# Power02.net
KiCad netlist of a schematic drawn in Altium Designer
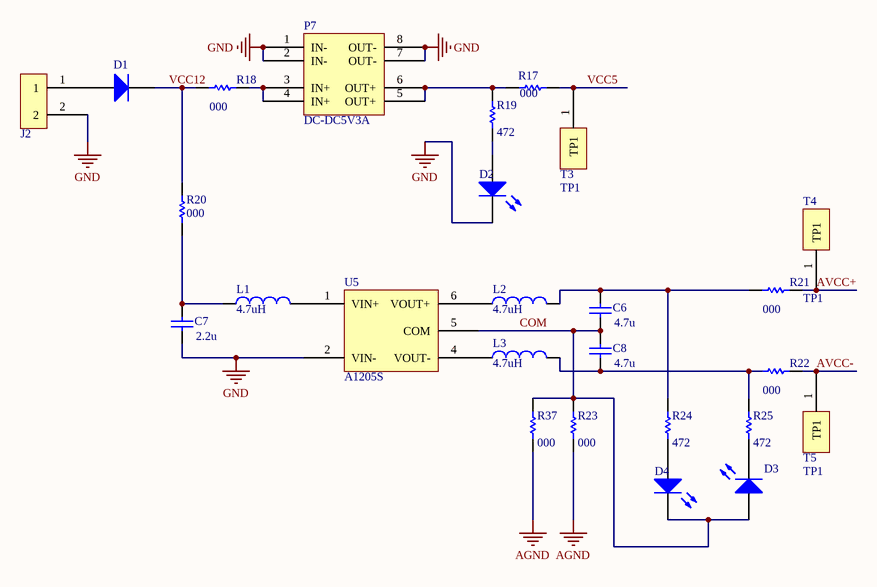
[diagram p0: Power02.SchDoc]

(export (version "E")
  (design (tool "Eeschema 10.0.6"))
  (components
    (comp (ref "C6")
      (value "4.7u")
      (footprint "1206")
      (description "Capacitor (Semiconductor SIM Model)")
      (fields (field (name "Comment") "Cap Semi") (field (name "PUBLISHER") "Altium Limited"))
      (libsource (lib "Miscellaneous Devices") (part "Cap Semi"))
    )
    (comp (ref "C7")
      (value "2.2u")
      (footprint "1206")
      (description "Capacitor (Semiconductor SIM Model)")
      (fields (field (name "Comment") "Cap Semi") (field (name "PUBLISHER") "Altium Limited"))
      (libsource (lib "Miscellaneous Devices") (part "Cap Semi"))
    )
    (comp (ref "C8")
      (value "4.7u")
      (footprint "1206")
      (description "Capacitor (Semiconductor SIM Model)")
      (fields (field (name "Comment") "Cap Semi") (field (name "PUBLISHER") "Altium Limited"))
      (libsource (lib "Miscellaneous Devices") (part "Cap Semi"))
    )
    (comp (ref "D1")
      (value "LED2")
      (footprint "0805_LED")
      (description "1 Amp General Purpose Rectifier")
      (fields (field (name "PUBLISHER") "Altium Limited"))
      (libsource (lib "Miscellaneous Devices") (part "Diode 1N4001"))
    )
    (comp (ref "D2")
      (value "LED2")
      (footprint "0805_LED")
      (description "Typical RED, GREEN, YELLOW, AMBER GaAs LED")
      (fields (field (name "PUBLISHER") "Altium Limited"))
      (libsource (lib "Miscellaneous Devices") (part "LED2"))
    )
    (comp (ref "D3")
      (value "LED2")
      (footprint "0805_LED")
      (description "Typical RED, GREEN, YELLOW, AMBER GaAs LED")
      (fields (field (name "PUBLISHER") "Altium Limited"))
      (libsource (lib "Miscellaneous Devices") (part "LED2"))
    )
    (comp (ref "D4")
      (value "LED2")
      (footprint "0805_LED")
      (description "Typical RED, GREEN, YELLOW, AMBER GaAs LED")
      (fields (field (name "PUBLISHER") "Altium Limited"))
      (libsource (lib "Miscellaneous Devices") (part "LED2"))
    )
    (comp (ref "J2") (value "XK7.62-2P") (footprint "XK7.62-2P") (libsource (lib "CHK-I") (part "XK7.62-2P")))
    (comp (ref "L1")
      (value "4.7uH")
      (footprint "1206")
      (description "Inductor")
      (fields (field (name "PUBLISHER") "Altium Limited"))
      (libsource (lib "Miscellaneous Devices") (part "Inductor"))
    )
    (comp (ref "L2")
      (value "4.7uH")
      (footprint "1206")
      (description "Inductor")
      (fields (field (name "PUBLISHER") "Altium Limited"))
      (libsource (lib "Miscellaneous Devices") (part "Inductor"))
    )
    (comp (ref "L3")
      (value "4.7uH")
      (footprint "1206")
      (description "Inductor")
      (fields (field (name "PUBLISHER") "Altium Limited"))
      (libsource (lib "Miscellaneous Devices") (part "Inductor"))
    )
    (comp (ref "P7") (value "DC-DC5V3A") (footprint "DC-DC3A") (libsource (lib "CHK-I") (part "DC-DC3A")))
    (comp (ref "R17")
      (value "000")
      (footprint "1206")
      (description "Semiconductor Resistor")
      (fields (field (name "Comment") "Res Semi") (field (name "PUBLISHER") "Altium Limited"))
      (libsource (lib "Miscellaneous Devices") (part "Res Semi"))
    )
    (comp (ref "R18")
      (value "000")
      (footprint "1206")
      (description "Semiconductor Resistor")
      (fields (field (name "Comment") "Res Semi") (field (name "PUBLISHER") "Altium Limited"))
      (libsource (lib "Miscellaneous Devices") (part "Res Semi"))
    )
    (comp (ref "R19")
      (value "472")
      (footprint "1206")
      (description "Semiconductor Resistor")
      (fields (field (name "Comment") "Res Semi") (field (name "PUBLISHER") "Altium Limited"))
      (libsource (lib "Miscellaneous Devices") (part "Res Semi"))
    )
    (comp (ref "R20")
      (value "000")
      (footprint "1206")
      (description "Semiconductor Resistor")
      (fields (field (name "Comment") "Res Semi") (field (name "PUBLISHER") "Altium Limited"))
      (libsource (lib "Miscellaneous Devices") (part "Res Semi"))
    )
    (comp (ref "R21")
      (value "000")
      (footprint "1206")
      (description "Semiconductor Resistor")
      (fields (field (name "Comment") "Res Semi") (field (name "PUBLISHER") "Altium Limited"))
      (libsource (lib "Miscellaneous Devices") (part "Res Semi"))
    )
    (comp (ref "R22")
      (value "000")
      (footprint "1206")
      (description "Semiconductor Resistor")
      (fields (field (name "Comment") "Res Semi") (field (name "PUBLISHER") "Altium Limited"))
      (libsource (lib "Miscellaneous Devices") (part "Res Semi"))
    )
    (comp (ref "R23")
      (value "000")
      (footprint "1206")
      (description "Semiconductor Resistor")
      (fields (field (name "Comment") "Res Semi") (field (name "PUBLISHER") "Altium Limited"))
      (libsource (lib "Miscellaneous Devices") (part "Res Semi"))
    )
    (comp (ref "R24")
      (value "472")
      (footprint "1206")
      (description "Semiconductor Resistor")
      (fields (field (name "Comment") "Res Semi") (field (name "PUBLISHER") "Altium Limited"))
      (libsource (lib "Miscellaneous Devices") (part "Res Semi"))
    )
    (comp (ref "R25")
      (value "472")
      (footprint "1206")
      (description "Semiconductor Resistor")
      (fields (field (name "Comment") "Res Semi") (field (name "PUBLISHER") "Altium Limited"))
      (libsource (lib "Miscellaneous Devices") (part "Res Semi"))
    )
    (comp (ref "R37")
      (value "000")
      (footprint "1206")
      (description "Semiconductor Resistor")
      (fields (field (name "Comment") "Res Semi") (field (name "PUBLISHER") "Altium Limited"))
      (libsource (lib "Miscellaneous Devices") (part "Res Semi"))
    )
    (comp (ref "T3") (value "TP1") (footprint "TP1") (libsource (lib "CHK-I") (part "TP1")))
    (comp (ref "T4") (value "TP1") (footprint "TP1") (libsource (lib "") (part "TP1_1")))
    (comp (ref "T5") (value "TP1") (footprint "TP1") (libsource (lib "CHK-I") (part "TP1")))
    (comp (ref "U5") (value "A1205S") (footprint "A1205S") (libsource (lib "CHK-I") (part "A1205S")))
  )
  (nets
    (net (code "1") (name "/AVCC+") (class "Default")
      (node (ref "R21") (pin "2") (pinfunction "2_2") (pintype "passive"))
      (node (ref "T4") (pin "1") (pinfunction "TP1_1") (pintype "passive"))
    )
    (net (code "2") (name "/AVCC-") (class "Default")
      (node (ref "R22") (pin "2") (pinfunction "2_2") (pintype "passive"))
      (node (ref "T5") (pin "1") (pinfunction "TP1_1") (pintype "passive"))
    )
    (net (code "3") (name "/COM") (class "Default")
      (node (ref "C6") (pin "1") (pinfunction "1_1") (pintype "passive"))
      (node (ref "C8") (pin "2") (pinfunction "2_2") (pintype "passive"))
      (node (ref "D3") (pin "1") (pinfunction "A_1") (pintype "passive"))
      (node (ref "D4") (pin "2") (pinfunction "K_2") (pintype "passive"))
      (node (ref "R23") (pin "2") (pinfunction "2_2") (pintype "passive"))
      (node (ref "R37") (pin "2") (pinfunction "2_2") (pintype "passive"))
      (node (ref "U5") (pin "5") (pinfunction "COM_5") (pintype "passive"))
    )
    (net (code "4") (name "/VCC5") (class "Default")
      (node (ref "R17") (pin "2") (pinfunction "2_2") (pintype "passive"))
      (node (ref "T3") (pin "1") (pinfunction "TP1_1") (pintype "passive"))
    )
    (net (code "5") (name "/VCC12") (class "Default")
      (node (ref "D1") (pin "2") (pinfunction "K_2") (pintype "passive"))
      (node (ref "R18") (pin "1") (pinfunction "1_1") (pintype "passive"))
      (node (ref "R20") (pin "2") (pinfunction "2_2") (pintype "passive"))
    )
    (net (code "6") (name "AGND") (class "Default")
      (node (ref "R23") (pin "1") (pinfunction "1_1") (pintype "passive"))
      (node (ref "R37") (pin "1") (pinfunction "1_1") (pintype "passive"))
    )
    (net (code "7") (name "GND") (class "Default")
      (node (ref "C7") (pin "1") (pinfunction "1_1") (pintype "passive"))
      (node (ref "D2") (pin "2") (pinfunction "K_2") (pintype "passive"))
      (node (ref "J2") (pin "2") (pinfunction "2_2") (pintype "passive"))
      (node (ref "P7") (pin "1") (pinfunction "IN-_1") (pintype "passive"))
      (node (ref "P7") (pin "2") (pinfunction "IN-_2") (pintype "passive"))
      (node (ref "P7") (pin "7") (pinfunction "OUT-_7") (pintype "passive"))
      (node (ref "P7") (pin "8") (pinfunction "OUT-_8") (pintype "passive"))
      (node (ref "U5") (pin "2") (pinfunction "VIN-_2") (pintype "passive"))
    )
    (net (code "8") (name "Net-(C6-Pad2)") (class "Default")
      (node (ref "C6") (pin "2") (pinfunction "2_2") (pintype "passive"))
      (node (ref "L2") (pin "2") (pinfunction "2_2") (pintype "passive"))
      (node (ref "R21") (pin "1") (pinfunction "1_1") (pintype "passive"))
      (node (ref "R24") (pin "2") (pinfunction "2_2") (pintype "passive"))
    )
    (net (code "9") (name "Net-(C7-Pad2)") (class "Default")
      (node (ref "C7") (pin "2") (pinfunction "2_2") (pintype "passive"))
      (node (ref "L1") (pin "1") (pinfunction "1_1") (pintype "passive"))
      (node (ref "R20") (pin "1") (pinfunction "1_1") (pintype "passive"))
    )
    (net (code "10") (name "Net-(C8-Pad1)") (class "Default")
      (node (ref "C8") (pin "1") (pinfunction "1_1") (pintype "passive"))
      (node (ref "L3") (pin "2") (pinfunction "2_2") (pintype "passive"))
      (node (ref "R22") (pin "1") (pinfunction "1_1") (pintype "passive"))
      (node (ref "R25") (pin "2") (pinfunction "2_2") (pintype "passive"))
    )
    (net (code "11") (name "Net-(D1-A)") (class "Default")
      (node (ref "D1") (pin "1") (pinfunction "A_1") (pintype "passive"))
      (node (ref "J2") (pin "1") (pinfunction "1_1") (pintype "passive"))
    )
    (net (code "12") (name "Net-(D2-A)") (class "Default")
      (node (ref "D2") (pin "1") (pinfunction "A_1") (pintype "passive"))
      (node (ref "R19") (pin "1") (pinfunction "1_1") (pintype "passive"))
    )
    (net (code "13") (name "Net-(D3-K)") (class "Default")
      (node (ref "D3") (pin "2") (pinfunction "K_2") (pintype "passive"))
      (node (ref "R25") (pin "1") (pinfunction "1_1") (pintype "passive"))
    )
    (net (code "14") (name "Net-(D4-A)") (class "Default")
      (node (ref "D4") (pin "1") (pinfunction "A_1") (pintype "passive"))
      (node (ref "R24") (pin "1") (pinfunction "1_1") (pintype "passive"))
    )
    (net (code "15") (name "Net-(P7-IN+-Pad3)") (class "Default")
      (node (ref "P7") (pin "3") (pinfunction "IN+_3") (pintype "passive"))
      (node (ref "P7") (pin "4") (pinfunction "IN+_4") (pintype "passive"))
      (node (ref "R18") (pin "2") (pinfunction "2_2") (pintype "passive"))
    )
    (net (code "16") (name "Net-(P7-OUT+-Pad5)") (class "Default")
      (node (ref "P7") (pin "5") (pinfunction "OUT+_5") (pintype "passive"))
      (node (ref "P7") (pin "6") (pinfunction "OUT+_6") (pintype "passive"))
      (node (ref "R17") (pin "1") (pinfunction "1_1") (pintype "passive"))
      (node (ref "R19") (pin "2") (pinfunction "2_2") (pintype "passive"))
    )
    (net (code "17") (name "Net-(U5-VIN+)") (class "Default")
      (node (ref "L1") (pin "2") (pinfunction "2_2") (pintype "passive"))
      (node (ref "U5") (pin "1") (pinfunction "VIN+_1") (pintype "passive"))
    )
    (net (code "18") (name "Net-(U5-VOUT+)") (class "Default")
      (node (ref "L2") (pin "1") (pinfunction "1_1") (pintype "passive"))
      (node (ref "U5") (pin "6") (pinfunction "VOUT+_6") (pintype "passive"))
    )
    (net (code "19") (name "Net-(U5-VOUT-)") (class "Default")
      (node (ref "L3") (pin "1") (pinfunction "1_1") (pintype "passive"))
      (node (ref "U5") (pin "4") (pinfunction "VOUT-_4") (pintype "passive"))
    )
  )
)
